# pentabug_1layer.net
KiCad netlist of a schematic drawn in EAGLE
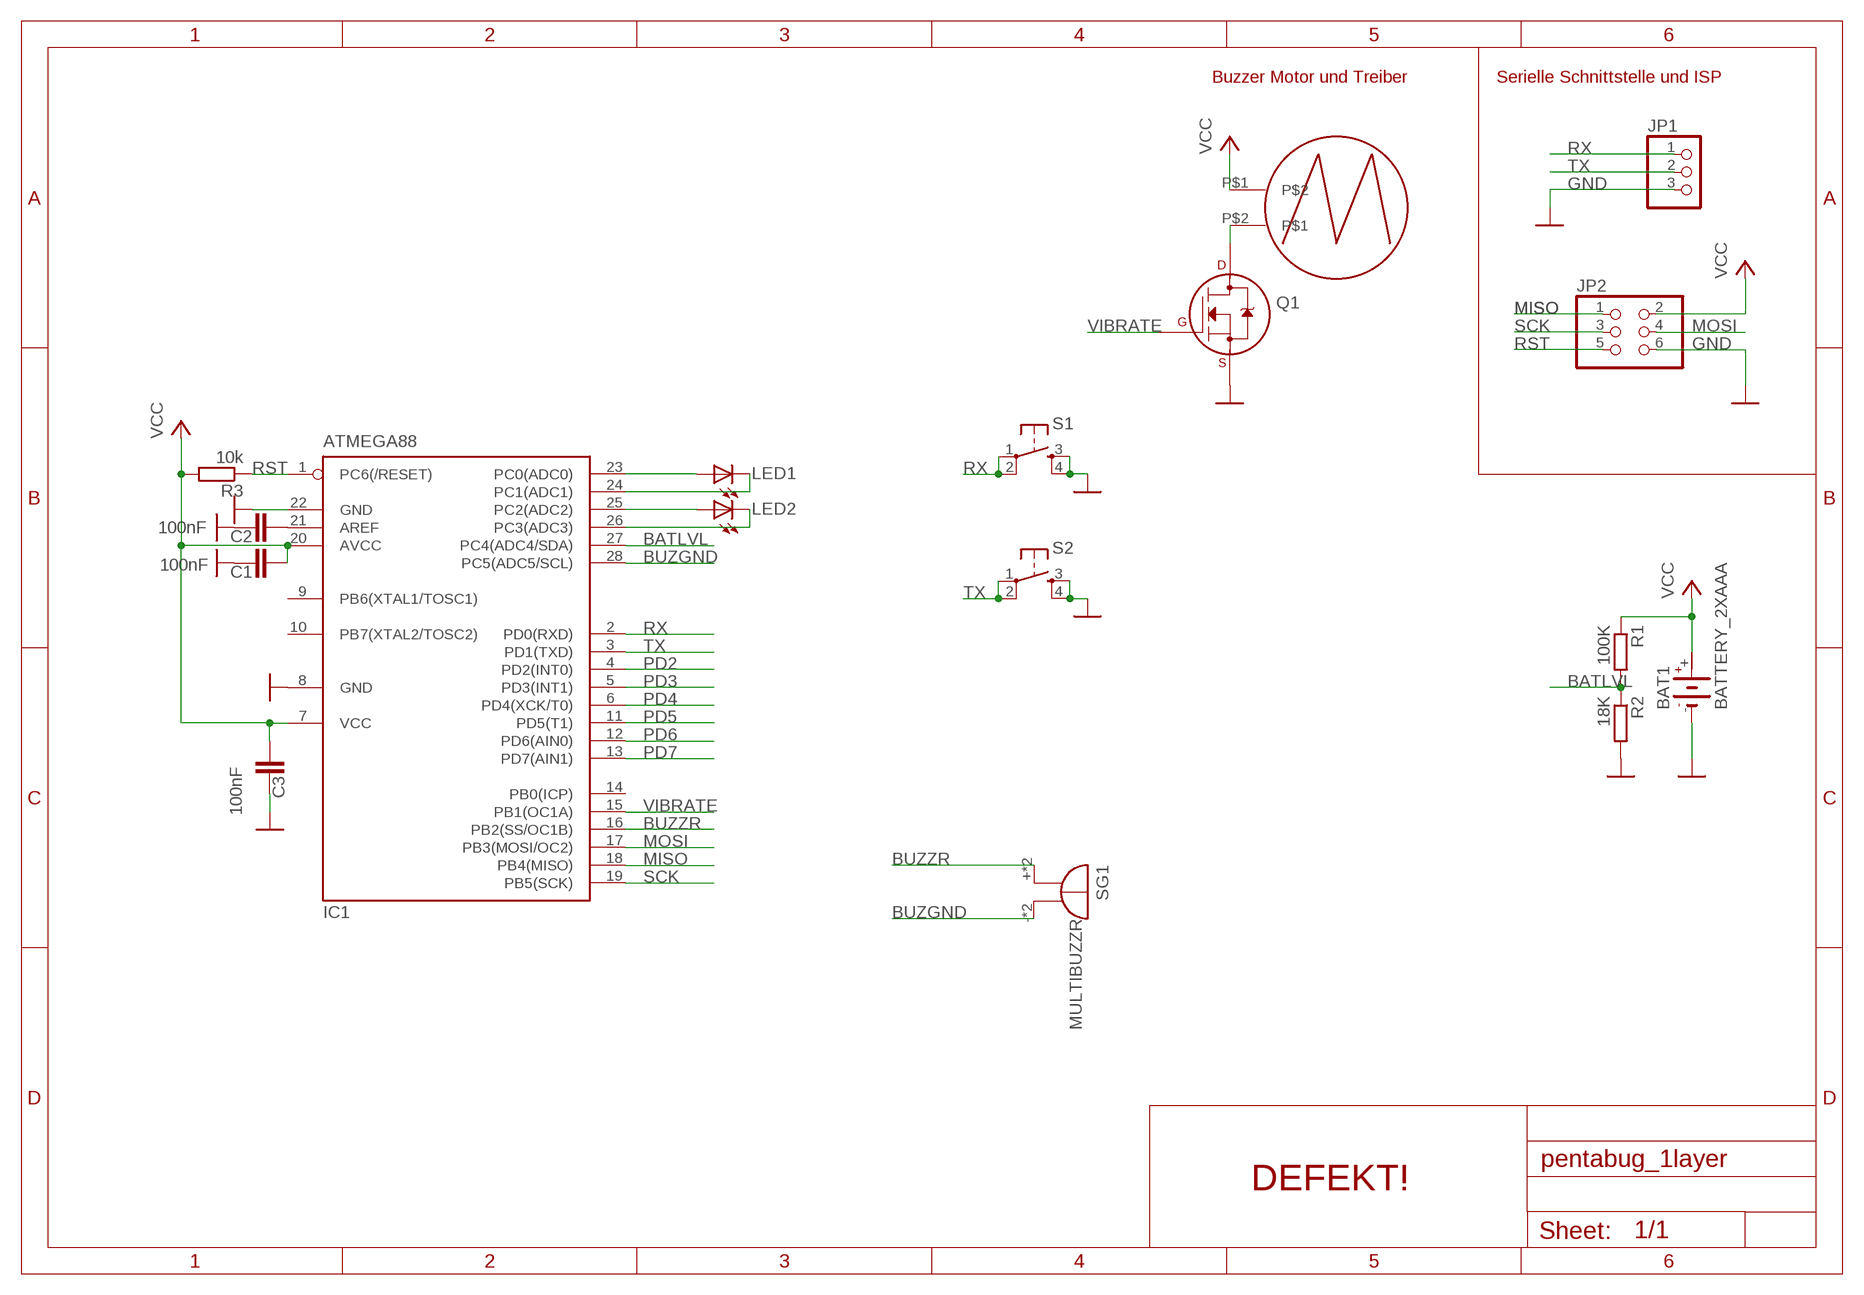
[diagram p0: schematic, sheet 1]

(export (version "E")
  (design (tool "Eeschema 10.0.6"))
  (components
    (comp (ref "BAT1")
      (value "BATTERY_2XAAA")
      (footprint "eagle-import:BATTERY_2XAAA")
      (libsource (lib "eagle-import") (part "BATTERY_2XAAA"))
    )
    (comp (ref "C1")
      (value "100nF")
      (footprint "eagle-import:C025-024X044")
      (libsource (lib "eagle-import") (part "C-EU025-024X044"))
    )
    (comp (ref "C2")
      (value "100nF")
      (footprint "eagle-import:C025-024X044")
      (libsource (lib "eagle-import") (part "C-EU025-024X044"))
    )
    (comp (ref "C3")
      (value "100nF")
      (footprint "eagle-import:C025-024X044")
      (libsource (lib "eagle-import") (part "C-EU025-024X044"))
    )
    (comp (ref "IC1")
      (value "ATMEGA88")
      (footprint "eagle-import:DIL28-3")
      (libsource (lib "eagle-import") (part "MEGA8-P"))
    )
    (comp (ref "JP1")
      (value "PINHD-1X3")
      (footprint "eagle-import:1X03")
      (libsource (lib "eagle-import") (part "PINHD-1X3"))
    )
    (comp (ref "JP2")
      (value "PINHD-2X3")
      (footprint "eagle-import:2X03")
      (libsource (lib "eagle-import") (part "PINHD-2X3"))
    )
    (comp (ref "LED1")
      (value "LED5MM")
      (footprint "eagle-import:LED5MM")
      (libsource (lib "eagle-import") (part "LED5MM"))
    )
    (comp (ref "LED2")
      (value "LED5MM")
      (footprint "eagle-import:LED5MM")
      (libsource (lib "eagle-import") (part "LED5MM"))
    )
    (comp (ref "Q1")
      (value "2N7000_TO92")
      (footprint "eagle-import:TO-92")
      (libsource (lib "eagle-import") (part "2N700_TO920"))
    )
    (comp (ref "R1")
      (value "100K")
      (footprint "eagle-import:0207_10")
      (libsource (lib "eagle-import") (part "R-EU_0207/10"))
    )
    (comp (ref "R2")
      (value "18K")
      (footprint "eagle-import:0207_10")
      (libsource (lib "eagle-import") (part "R-EU_0207/10"))
    )
    (comp (ref "R3")
      (value "10k")
      (footprint "eagle-import:0207_10")
      (libsource (lib "eagle-import") (part "R-EU_0207/10"))
    )
    (comp (ref "S1")
      (value "TAC_SWITCHPTH")
      (footprint "eagle-import:TACTILE-PTH")
      (libsource (lib "eagle-import") (part "TAC_SWITCHPTH"))
    )
    (comp (ref "S2")
      (value "TAC_SWITCHPTH")
      (footprint "eagle-import:TACTILE-PTH")
      (libsource (lib "eagle-import") (part "TAC_SWITCHPTH"))
    )
    (comp (ref "SG1")
      (value "MULTIBUZZR")
      (footprint "eagle-import:MULTIBUZZR")
      (libsource (lib "eagle-import") (part "MULTIBUZZR"))
    )
    (comp (ref "U$1")
      (value "VIBRAMOTOR")
      (footprint "eagle-import:LA4-432")
      (libsource (lib "eagle-import") (part "VIBRAMOTOR"))
    )
  )
  (nets
    (net (code "1") (name "/BATLVL") (class "Default")
      (node (ref "IC1") (pin "27") (pinfunction "PC4(ADC4/SDA)_27") (pintype "bidirectional"))
      (node (ref "R1") (pin "2") (pinfunction "2_2") (pintype "passive"))
      (node (ref "R2") (pin "1") (pinfunction "1_1") (pintype "passive"))
    )
    (net (code "2") (name "/BUZGND") (class "Default")
      (node (ref "IC1") (pin "28") (pinfunction "PC5(ADC5/SCL)_28") (pintype "bidirectional"))
      (node (ref "SG1") (pin "-") (pinfunction "-_-") (pintype "passive"))
      (node (ref "SG1") (pin "-1") (pinfunction "-_-1") (pintype "passive"))
    )
    (net (code "3") (name "/BUZZR") (class "Default")
      (node (ref "IC1") (pin "16") (pinfunction "PB2(SS/OC1B)_16") (pintype "bidirectional"))
      (node (ref "SG1") (pin "+") (pinfunction "+_+") (pintype "passive"))
      (node (ref "SG1") (pin "+1") (pinfunction "+_+1") (pintype "passive"))
    )
    (net (code "4") (name "/MISO") (class "Default")
      (node (ref "IC1") (pin "18") (pinfunction "PB4(MISO)_18") (pintype "bidirectional"))
      (node (ref "JP2") (pin "1") (pinfunction "1_1") (pintype "passive"))
    )
    (net (code "5") (name "/MOSI") (class "Default")
      (node (ref "IC1") (pin "17") (pinfunction "PB3(MOSI/OC2)_17") (pintype "bidirectional"))
      (node (ref "JP2") (pin "4") (pinfunction "4_4") (pintype "passive"))
    )
    (net (code "6") (name "/PD2") (class "Default")
      (node (ref "IC1") (pin "4") (pinfunction "PD2(INT0)_4") (pintype "bidirectional"))
    )
    (net (code "7") (name "/PD3") (class "Default")
      (node (ref "IC1") (pin "5") (pinfunction "PD3(INT1)_5") (pintype "bidirectional"))
    )
    (net (code "8") (name "/PD4") (class "Default")
      (node (ref "IC1") (pin "6") (pinfunction "PD4(XCK/T0)_6") (pintype "bidirectional"))
    )
    (net (code "9") (name "/PD5") (class "Default")
      (node (ref "IC1") (pin "11") (pinfunction "PD5(T1)_11") (pintype "bidirectional"))
    )
    (net (code "10") (name "/PD6") (class "Default")
      (node (ref "IC1") (pin "12") (pinfunction "PD6(AIN0)_12") (pintype "bidirectional"))
    )
    (net (code "11") (name "/PD7") (class "Default")
      (node (ref "IC1") (pin "13") (pinfunction "PD7(AIN1)_13") (pintype "bidirectional"))
    )
    (net (code "12") (name "/RST") (class "Default")
      (node (ref "IC1") (pin "1") (pinfunction "PC6(/RESET)_1") (pintype "bidirectional"))
      (node (ref "JP2") (pin "5") (pinfunction "5_5") (pintype "passive"))
      (node (ref "R3") (pin "1") (pinfunction "1_1") (pintype "passive"))
    )
    (net (code "13") (name "/RX") (class "Default")
      (node (ref "IC1") (pin "2") (pinfunction "PD0(RXD)_2") (pintype "bidirectional"))
      (node (ref "JP1") (pin "1") (pinfunction "1_1") (pintype "passive"))
      (node (ref "S1") (pin "1") (pinfunction "1_1") (pintype "passive"))
      (node (ref "S1") (pin "2") (pinfunction "2_2") (pintype "passive"))
    )
    (net (code "14") (name "/SCK") (class "Default")
      (node (ref "IC1") (pin "19") (pinfunction "PB5(SCK)_19") (pintype "bidirectional"))
      (node (ref "JP2") (pin "3") (pinfunction "3_3") (pintype "passive"))
    )
    (net (code "15") (name "/TX") (class "Default")
      (node (ref "IC1") (pin "3") (pinfunction "PD1(TXD)_3") (pintype "bidirectional"))
      (node (ref "JP1") (pin "2") (pinfunction "2_2") (pintype "passive"))
      (node (ref "S2") (pin "1") (pinfunction "1_1") (pintype "passive"))
      (node (ref "S2") (pin "2") (pinfunction "2_2") (pintype "passive"))
    )
    (net (code "16") (name "/VIBRATE") (class "Default")
      (node (ref "IC1") (pin "15") (pinfunction "PB1(OC1A)_15") (pintype "bidirectional"))
      (node (ref "Q1") (pin "2") (pinfunction "G_2") (pintype "tri_state"))
    )
    (net (code "17") (name "GND") (class "Default")
      (node (ref "BAT1") (pin "-") (pinfunction "-_-") (pintype "passive"))
      (node (ref "C1") (pin "1") (pinfunction "1_1") (pintype "passive"))
      (node (ref "C2") (pin "1") (pinfunction "1_1") (pintype "passive"))
      (node (ref "C3") (pin "1") (pinfunction "1_1") (pintype "passive"))
      (node (ref "IC1") (pin "22") (pinfunction "GND_22") (pintype "power_in"))
      (node (ref "IC1") (pin "8") (pinfunction "GND_8") (pintype "power_in"))
      (node (ref "JP1") (pin "3") (pinfunction "3_3") (pintype "passive"))
      (node (ref "JP2") (pin "6") (pinfunction "6_6") (pintype "passive"))
      (node (ref "Q1") (pin "1") (pinfunction "S_1") (pintype "bidirectional"))
      (node (ref "R2") (pin "2") (pinfunction "2_2") (pintype "passive"))
      (node (ref "S1") (pin "3") (pinfunction "3_3") (pintype "passive"))
      (node (ref "S1") (pin "4") (pinfunction "4_4") (pintype "passive"))
      (node (ref "S2") (pin "3") (pinfunction "3_3") (pintype "passive"))
      (node (ref "S2") (pin "4") (pinfunction "4_4") (pintype "passive"))
    )
    (net (code "18") (name "Net-(IC1-AREF)") (class "Default")
      (node (ref "C2") (pin "2") (pinfunction "2_2") (pintype "passive"))
      (node (ref "IC1") (pin "21") (pinfunction "AREF_21") (pintype "passive"))
    )
    (net (code "19") (name "Net-(IC1-PC0(ADC0))") (class "Default")
      (node (ref "IC1") (pin "23") (pinfunction "PC0(ADC0)_23") (pintype "bidirectional"))
      (node (ref "LED1") (pin "A") (pinfunction "A_A") (pintype "passive"))
    )
    (net (code "20") (name "Net-(IC1-PC1(ADC1))") (class "Default")
      (node (ref "IC1") (pin "24") (pinfunction "PC1(ADC1)_24") (pintype "bidirectional"))
      (node (ref "LED1") (pin "K") (pinfunction "C_K") (pintype "passive"))
    )
    (net (code "21") (name "Net-(IC1-PC2(ADC2))") (class "Default")
      (node (ref "IC1") (pin "25") (pinfunction "PC2(ADC2)_25") (pintype "bidirectional"))
      (node (ref "LED2") (pin "A") (pinfunction "A_A") (pintype "passive"))
    )
    (net (code "22") (name "Net-(IC1-PC3(ADC3))") (class "Default")
      (node (ref "IC1") (pin "26") (pinfunction "PC3(ADC3)_26") (pintype "bidirectional"))
      (node (ref "LED2") (pin "K") (pinfunction "C_K") (pintype "passive"))
    )
    (net (code "23") (name "Net-(Q1-D)") (class "Default")
      (node (ref "Q1") (pin "3") (pinfunction "D_3") (pintype "bidirectional"))
      (node (ref "U$1") (pin "P$2") (pinfunction "P$1_P$2") (pintype "power_in"))
    )
    (net (code "24") (name "VCC") (class "Default")
      (node (ref "BAT1") (pin "+") (pinfunction "+_+") (pintype "passive"))
      (node (ref "C1") (pin "2") (pinfunction "2_2") (pintype "passive"))
      (node (ref "C3") (pin "2") (pinfunction "2_2") (pintype "passive"))
      (node (ref "IC1") (pin "20") (pinfunction "AVCC_20") (pintype "power_in"))
      (node (ref "IC1") (pin "7") (pinfunction "VCC_7") (pintype "power_in"))
      (node (ref "JP2") (pin "2") (pinfunction "2_2") (pintype "passive"))
      (node (ref "R1") (pin "1") (pinfunction "1_1") (pintype "passive"))
      (node (ref "R3") (pin "2") (pinfunction "2_2") (pintype "passive"))
      (node (ref "U$1") (pin "P$1") (pinfunction "P$2_P$1") (pintype "power_in"))
    )
    (net (code "25") (name "unconnected-(IC1-PB0(ICP)-Pad14)") (class "Default")
      (node (ref "IC1") (pin "14") (pinfunction "PB0(ICP)_14") (pintype "bidirectional"))
    )
    (net (code "26") (name "unconnected-(IC1-PB6(XTAL1{slash}TOSC1)-Pad9)") (class "Default")
      (node (ref "IC1") (pin "9") (pinfunction "PB6(XTAL1/TOSC1)_9") (pintype "bidirectional"))
    )
    (net (code "27") (name "unconnected-(IC1-PB7(XTAL2{slash}TOSC2)-Pad10)") (class "Default")
      (node (ref "IC1") (pin "10") (pinfunction "PB7(XTAL2/TOSC2)_10") (pintype "bidirectional"))
    )
  )
)
